# CATS-FAT-CAN.net
KiCad netlist of a schematic drawn in Altium Designer
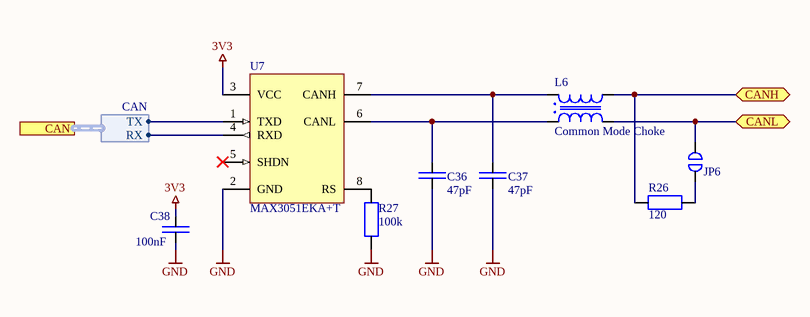
[diagram p0: CATS-FAT-CAN.SchDoc]

(export (version "E")
  (design (tool "Eeschema 10.0.6"))
  (components
    (comp (ref "C36")
      (value "47pF")
      (footprint "SMD Keramikkondensator 0603")
      (description "SMD Ceramic Capacitor E6")
      (libsource (lib "Ceramic Capacitors-E6") (part "E6 - 47pF"))
    )
    (comp (ref "C37")
      (value "47pF")
      (footprint "SMD Keramikkondensator 0603")
      (description "SMD Ceramic Capacitor E6")
      (libsource (lib "Ceramic Capacitors-E6") (part "E6 - 47pF"))
    )
    (comp (ref "C38")
      (value "100nF")
      (footprint "SMD Keramikkondensator 0603")
      (description "SMD Ceramic Capacitor E6")
      (libsource (lib "Ceramic Capacitors-E6") (part "E6 - 100nF"))
    )
    (comp (ref "JP6")
      (value "Jumper")
      (footprint "SMD Solder Jumper 1x2mm")
      (description "Single Position Jumper")
      (libsource (lib "Connectors") (part "Jumper-1"))
    )
    (comp (ref "L6")
      (value "Common Mode Choke")
      (footprint "SMD Common Mode Choke 2x1.2")
      (description "2 Line Common Mode Choke Surface Mount 370mA DCR 300mOhm")
      (libsource (lib "Inductors") (part "Common Mode Choke (CAN)"))
    )
    (comp (ref "R26")
      (value "120")
      (footprint "SMD Widerstand 0603")
      (description "SMD Chip Resistor E24")
      (libsource (lib "Resistors-E24") (part "E24 - 120"))
    )
    (comp (ref "R27")
      (value "100k")
      (footprint "SMD Widerstand 0603")
      (description "SMD Chip Resistor E24")
      (libsource (lib "Resistors-E24") (part "E24 - 100k"))
    )
    (comp (ref "U7")
      (value "MAX3051EKA+T")
      (footprint "SMD IC SOT-23-8")
      (description "+3.3V, 1Mbps, Low-Supply-Current\r\nCAN Transceiver")
      (libsource (lib "Communication") (part "MAX3051EKA+T"))
    )
  )
  (nets
    (net (code "2") (name "/CANH") (class "Default")
      (node (ref "L6") (pin "3") (pinfunction "3_3") (pintype "passive"))
      (node (ref "R26") (pin "1") (pinfunction "1_1") (pintype "passive"))
    )
    (net (code "3") (name "/CANL") (class "Default")
      (node (ref "JP6") (pin "1") (pintype "passive"))
      (node (ref "L6") (pin "2") (pinfunction "2_2") (pintype "passive"))
    )
    (net (code "4") (name "/RX") (class "Default")
      (node (ref "U7") (pin "4") (pinfunction "RXD_4") (pintype "output"))
    )
    (net (code "5") (name "/TX") (class "Default")
      (node (ref "U7") (pin "1") (pinfunction "TXD_1") (pintype "input"))
    )
    (net (code "7") (name "3V3") (class "Default")
      (node (ref "C38") (pin "2") (pinfunction "2_2") (pintype "passive"))
      (node (ref "U7") (pin "3") (pinfunction "VCC_3") (pintype "passive"))
    )
    (net (code "8") (name "GND") (class "Default")
      (node (ref "C36") (pin "1") (pinfunction "1_1") (pintype "passive"))
      (node (ref "C37") (pin "1") (pinfunction "1_1") (pintype "passive"))
      (node (ref "C38") (pin "1") (pinfunction "1_1") (pintype "passive"))
      (node (ref "R27") (pin "1") (pinfunction "1_1") (pintype "passive"))
      (node (ref "U7") (pin "2") (pinfunction "GND_2") (pintype "passive"))
    )
    (net (code "9") (name "Net-(JP6-Pad2)") (class "Default")
      (node (ref "JP6") (pin "2") (pintype "passive"))
      (node (ref "R26") (pin "2") (pinfunction "2_2") (pintype "passive"))
    )
    (net (code "10") (name "Net-(U7-CANH)") (class "Default")
      (node (ref "C37") (pin "2") (pinfunction "2_2") (pintype "passive"))
      (node (ref "L6") (pin "4") (pinfunction "4_4") (pintype "passive"))
      (node (ref "U7") (pin "7") (pinfunction "CANH_7") (pintype "passive"))
    )
    (net (code "11") (name "Net-(U7-CANL)") (class "Default")
      (node (ref "C36") (pin "2") (pinfunction "2_2") (pintype "passive"))
      (node (ref "L6") (pin "1") (pinfunction "1_1") (pintype "passive"))
      (node (ref "U7") (pin "6") (pinfunction "CANL_6") (pintype "passive"))
    )
    (net (code "12") (name "Net-(U7-RS)") (class "Default")
      (node (ref "R27") (pin "2") (pinfunction "2_2") (pintype "passive"))
      (node (ref "U7") (pin "8") (pinfunction "RS_8") (pintype "passive"))
    )
    (net (code "13") (name "unconnected-(U7-SHDN-Pad5)") (class "Default")
      (node (ref "U7") (pin "5") (pinfunction "SHDN_5") (pintype "input+no_connect"))
    )
  )
)
